# MYC_FS20.net
KiCad netlist of a schematic drawn in EAGLE
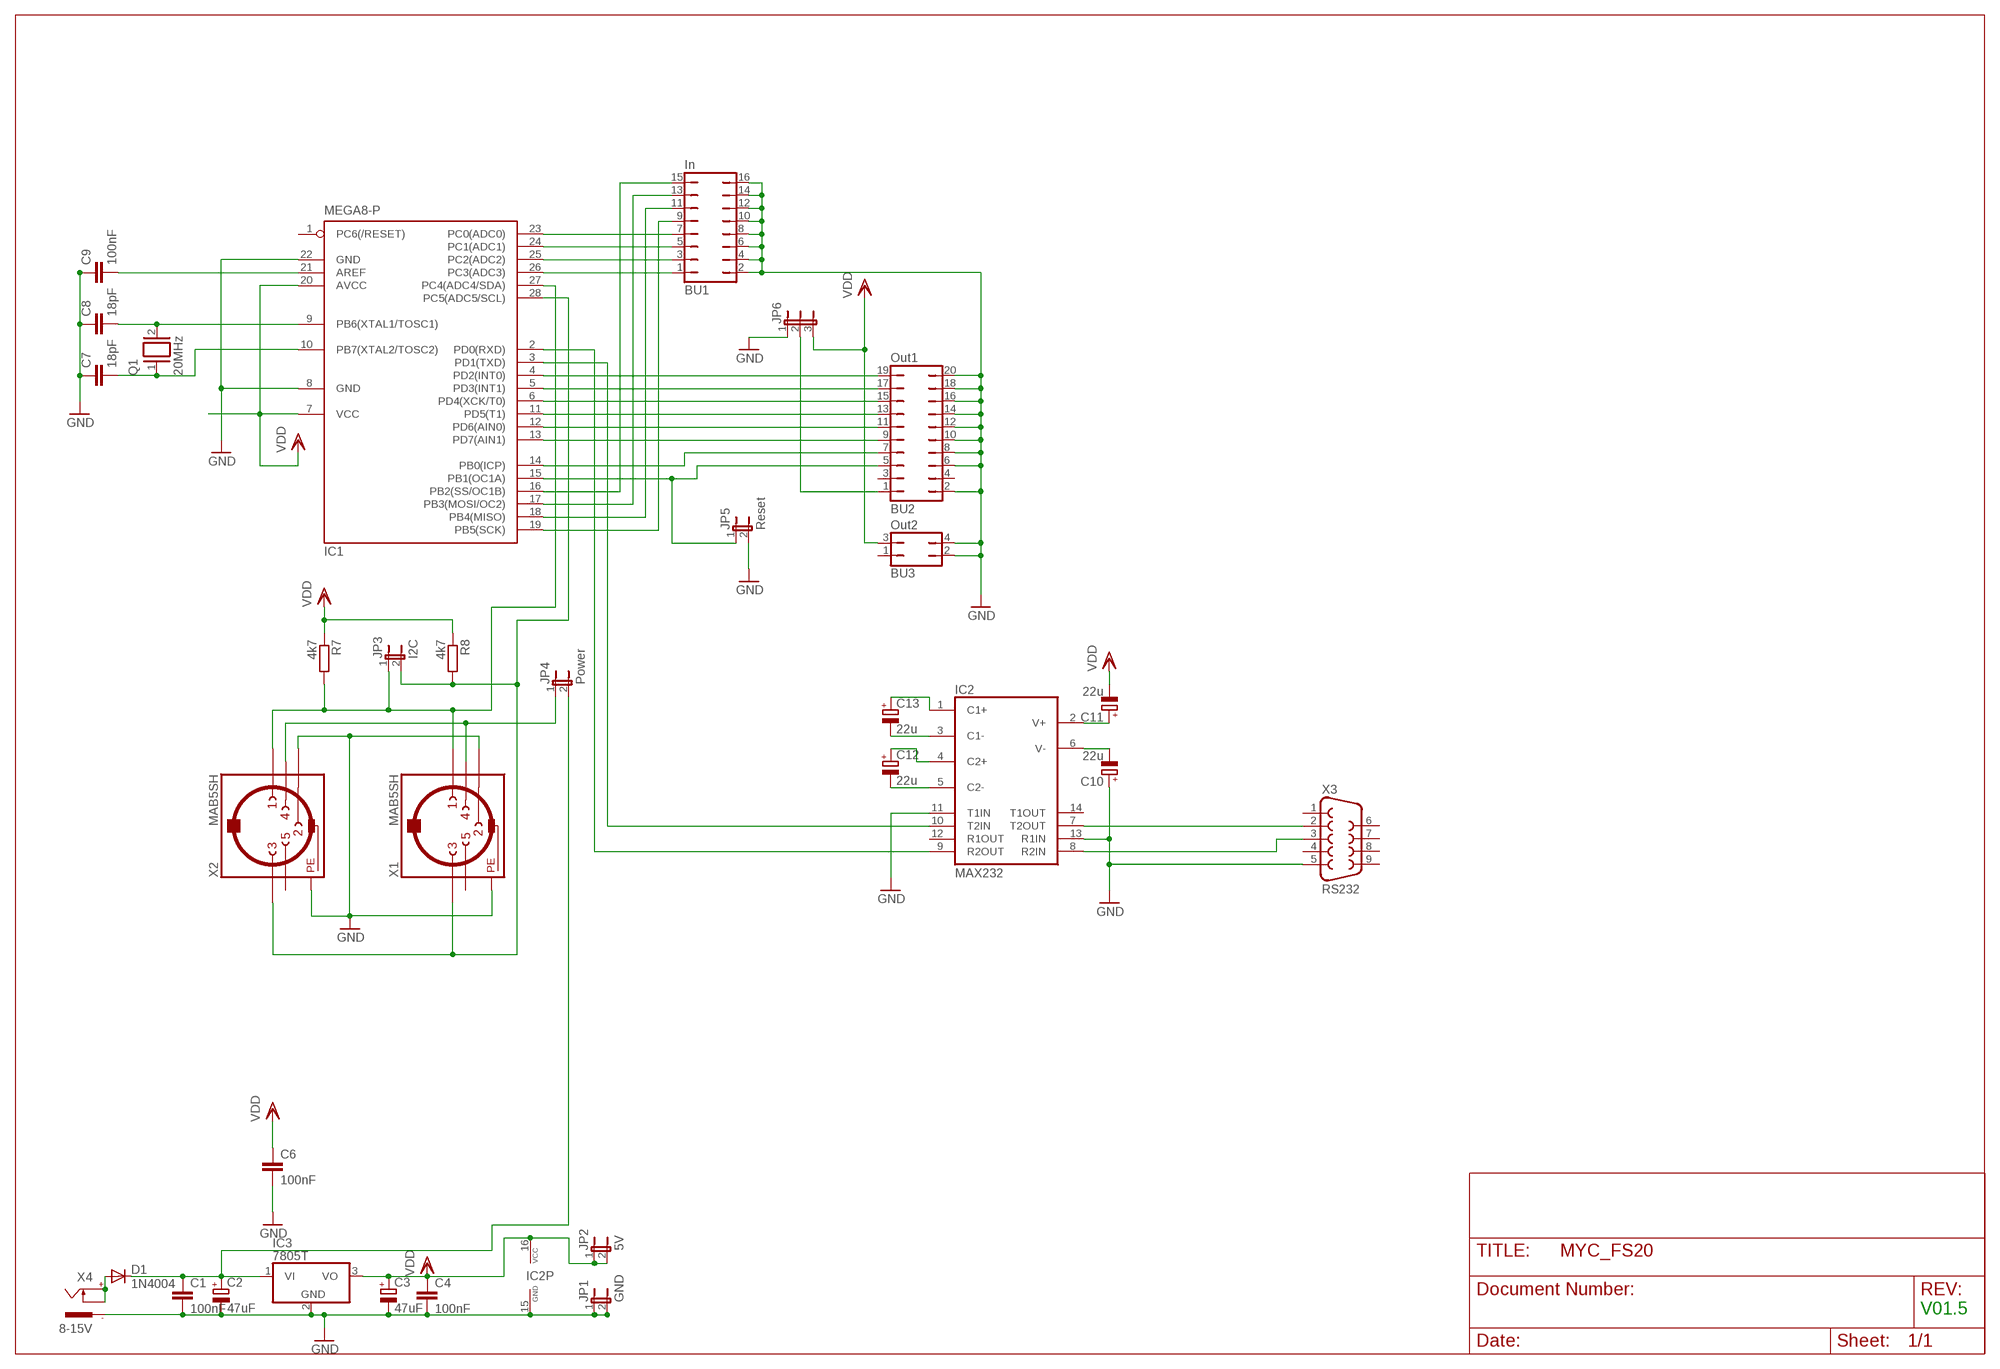
[diagram p0: schematic, sheet 1]

(export (version "E")
  (design (tool "Eeschema 10.0.6"))
  (components
    (comp (ref "BU1")
      (value "In")
      (footprint "eagle-import:JP8Q")
      (libsource (lib "eagle-import") (part "JP8Q"))
    )
    (comp (ref "BU2")
      (value "Out1")
      (footprint "eagle-import:JP10Q")
      (libsource (lib "eagle-import") (part "JP10Q"))
    )
    (comp (ref "BU3")
      (value "Out2")
      (footprint "eagle-import:JP2Q")
      (libsource (lib "eagle-import") (part "JP2Q"))
    )
    (comp (ref "C1")
      (value "100nF")
      (footprint "eagle-import:C050-025X075")
      (libsource (lib "eagle-import") (part "C-EU050-025X075"))
    )
    (comp (ref "C2")
      (value "47uF")
      (footprint "eagle-import:TT5D10")
      (libsource (lib "eagle-import") (part "CPOL-EUTT5D10"))
    )
    (comp (ref "C3")
      (value "47uF")
      (footprint "eagle-import:TT5D10")
      (libsource (lib "eagle-import") (part "CPOL-EUTT5D10"))
    )
    (comp (ref "C4")
      (value "100nF")
      (footprint "eagle-import:C050-025X075")
      (libsource (lib "eagle-import") (part "C-EU050-025X075"))
    )
    (comp (ref "C6")
      (value "100nF")
      (footprint "eagle-import:C050-025X075")
      (libsource (lib "eagle-import") (part "C-EU050-025X075"))
    )
    (comp (ref "C7")
      (value "18pF")
      (footprint "eagle-import:C050-025X075")
      (libsource (lib "eagle-import") (part "C-EU050-025X075"))
    )
    (comp (ref "C8")
      (value "18pF")
      (footprint "eagle-import:C050-025X075")
      (libsource (lib "eagle-import") (part "C-EU050-025X075"))
    )
    (comp (ref "C9")
      (value "100nF")
      (footprint "eagle-import:C050-025X075")
      (libsource (lib "eagle-import") (part "C-EU050-025X075"))
    )
    (comp (ref "C10")
      (value "22u")
      (footprint "eagle-import:TT5D7")
      (libsource (lib "eagle-import") (part "CPOL-EUTT5D7"))
    )
    (comp (ref "C11")
      (value "22u")
      (footprint "eagle-import:TT5D7")
      (libsource (lib "eagle-import") (part "CPOL-EUTT5D7"))
    )
    (comp (ref "C12")
      (value "22u")
      (footprint "eagle-import:TT5D7")
      (libsource (lib "eagle-import") (part "CPOL-EUTT5D7"))
    )
    (comp (ref "C13")
      (value "22u")
      (footprint "eagle-import:TT5D7")
      (libsource (lib "eagle-import") (part "CPOL-EUTT5D7"))
    )
    (comp (ref "D1")
      (value "1N4004")
      (footprint "eagle-import:DO41-10")
      (libsource (lib "eagle-import") (part "1N4004"))
    )
    (comp (ref "IC1")
      (value "MEGA8-P")
      (footprint "eagle-import:DIL28-3")
      (libsource (lib "eagle-import") (part "MEGA8-P"))
    )
    (comp (ref "IC2")
      (value "MAX232")
      (footprint "eagle-import:DIL16")
      (fields (field (name "MF") "MAXIM") (field (name "MPN") "MAX232ACPE+"))
      (libsource (lib "eagle-import") (part "MAX232"))
    )
    (comp (ref "IC3")
      (value "7805T")
      (footprint "eagle-import:TO220H")
      (libsource (lib "eagle-import") (part "78T05"))
    )
    (comp (ref "JP1")
      (value "GND")
      (footprint "eagle-import:JP1")
      (libsource (lib "eagle-import") (part "JP1E"))
    )
    (comp (ref "JP2")
      (value "5V")
      (footprint "eagle-import:JP1")
      (libsource (lib "eagle-import") (part "JP1E"))
    )
    (comp (ref "JP3")
      (value "I2C")
      (footprint "eagle-import:JP1")
      (libsource (lib "eagle-import") (part "JP1E"))
    )
    (comp (ref "JP4")
      (value "Power")
      (footprint "eagle-import:JP1")
      (libsource (lib "eagle-import") (part "JP1E"))
    )
    (comp (ref "JP5")
      (value "Reset")
      (footprint "eagle-import:JP1")
      (libsource (lib "eagle-import") (part "JP1E"))
    )
    (comp (ref "JP6")
      (value "JP2E")
      (footprint "eagle-import:JP2")
      (libsource (lib "eagle-import") (part "JP2E"))
    )
    (comp (ref "Q1")
      (value "20MHz")
      (footprint "eagle-import:QS")
      (libsource (lib "eagle-import") (part "XTAL/S"))
    )
    (comp (ref "R7")
      (value "4k7")
      (footprint "eagle-import:0207_5V")
      (libsource (lib "eagle-import") (part "R-EU_0207/5V"))
    )
    (comp (ref "R8")
      (value "4k7")
      (footprint "eagle-import:0207_5V")
      (libsource (lib "eagle-import") (part "R-EU_0207/5V"))
    )
    (comp (ref "X1")
      (value "MAB5SH")
      (footprint "eagle-import:MAB5SH")
      (libsource (lib "eagle-import") (part "MAB5SH"))
    )
    (comp (ref "X2")
      (value "MAB5SH")
      (footprint "eagle-import:MAB5SH")
      (libsource (lib "eagle-import") (part "MAB5SH"))
    )
    (comp (ref "X3")
      (value "RS232")
      (footprint "eagle-import:F09H")
      (libsource (lib "eagle-import") (part "F09H"))
    )
    (comp (ref "X4")
      (value "8-15V")
      (footprint "eagle-import:737992-5")
      (libsource (lib "eagle-import") (part "737992-55"))
    )
  )
  (nets
    (net (code "1") (name "GND") (class "Default")
      (node (ref "BU1") (pin "10") (pinfunction "10_10") (pintype "passive"))
      (node (ref "BU1") (pin "12") (pinfunction "12_12") (pintype "passive"))
      (node (ref "BU1") (pin "14") (pinfunction "14_14") (pintype "passive"))
      (node (ref "BU1") (pin "16") (pinfunction "16_16") (pintype "passive"))
      (node (ref "BU1") (pin "2") (pinfunction "2_2") (pintype "passive"))
      (node (ref "BU1") (pin "4") (pinfunction "4_4") (pintype "passive"))
      (node (ref "BU1") (pin "6") (pinfunction "6_6") (pintype "passive"))
      (node (ref "BU1") (pin "8") (pinfunction "8_8") (pintype "passive"))
      (node (ref "BU2") (pin "10") (pinfunction "10_10") (pintype "passive"))
      (node (ref "BU2") (pin "12") (pinfunction "12_12") (pintype "passive"))
      (node (ref "BU2") (pin "14") (pinfunction "14_14") (pintype "passive"))
      (node (ref "BU2") (pin "16") (pinfunction "16_16") (pintype "passive"))
      (node (ref "BU2") (pin "18") (pinfunction "18_18") (pintype "passive"))
      (node (ref "BU2") (pin "2") (pinfunction "2_2") (pintype "passive"))
      (node (ref "BU2") (pin "20") (pinfunction "20_20") (pintype "passive"))
      (node (ref "BU2") (pin "6") (pinfunction "6_6") (pintype "passive"))
      (node (ref "BU2") (pin "8") (pinfunction "8_8") (pintype "passive"))
      (node (ref "BU3") (pin "2") (pinfunction "2_2") (pintype "passive"))
      (node (ref "BU3") (pin "4") (pinfunction "4_4") (pintype "passive"))
      (node (ref "C1") (pin "2") (pinfunction "2_2") (pintype "passive"))
      (node (ref "C10") (pin "+") (pinfunction "+_+") (pintype "passive"))
      (node (ref "C2") (pin "-") (pinfunction "-_-") (pintype "passive"))
      (node (ref "C3") (pin "-") (pinfunction "-_-") (pintype "passive"))
      (node (ref "C4") (pin "2") (pinfunction "2_2") (pintype "passive"))
      (node (ref "C6") (pin "2") (pinfunction "2_2") (pintype "passive"))
      (node (ref "C7") (pin "1") (pinfunction "1_1") (pintype "passive"))
      (node (ref "C8") (pin "1") (pinfunction "1_1") (pintype "passive"))
      (node (ref "C9") (pin "1") (pinfunction "1_1") (pintype "passive"))
      (node (ref "IC1") (pin "22") (pinfunction "GND_22") (pintype "power_in"))
      (node (ref "IC1") (pin "8") (pinfunction "GND_8") (pintype "power_in"))
      (node (ref "IC2") (pin "11") (pinfunction "T1IN_11") (pintype "input"))
      (node (ref "IC2") (pin "13") (pinfunction "R1IN_13") (pintype "input"))
      (node (ref "IC2") (pin "15") (pinfunction "GND_15") (pintype "power_in"))
      (node (ref "IC3") (pin "2") (pinfunction "GND_2") (pintype "passive"))
      (node (ref "JP1") (pin "1") (pinfunction "1_1") (pintype "passive"))
      (node (ref "JP1") (pin "2") (pinfunction "2_2") (pintype "passive"))
      (node (ref "JP5") (pin "2") (pinfunction "2_2") (pintype "passive"))
      (node (ref "JP6") (pin "1") (pinfunction "1_1") (pintype "passive"))
      (node (ref "X1") (pin "2") (pinfunction "2_2") (pintype "passive"))
      (node (ref "X1") (pin "PE") (pinfunction "PE_PE") (pintype "power_in"))
      (node (ref "X1") (pin "PE@") (pinfunction "PE_PE@") (pintype "power_in"))
      (node (ref "X2") (pin "2") (pinfunction "2_2") (pintype "passive"))
      (node (ref "X2") (pin "PE") (pinfunction "PE_PE") (pintype "power_in"))
      (node (ref "X2") (pin "PE@") (pinfunction "PE_PE@") (pintype "power_in"))
      (node (ref "X3") (pin "5") (pinfunction "5_5") (pintype "passive"))
      (node (ref "X4") (pin "-1") (pinfunction "-1_-1") (pintype "passive"))
    )
    (net (code "2") (name "Net-(BU2-Pad1)") (class "Default")
      (node (ref "BU2") (pin "1") (pinfunction "1_1") (pintype "passive"))
      (node (ref "JP6") (pin "2") (pinfunction "2_2") (pintype "passive"))
    )
    (net (code "3") (name "Net-(D1-PadA)") (class "Default")
      (node (ref "D1") (pin "A") (pinfunction "A_A") (pintype "passive"))
      (node (ref "X4") (pin "+") (pinfunction "+_+") (pintype "passive"))
      (node (ref "X4") (pin "K") (pinfunction "K_K") (pintype "passive"))
    )
    (net (code "4") (name "Net-(IC1-AREF)") (class "Default")
      (node (ref "C9") (pin "2") (pinfunction "2_2") (pintype "passive"))
      (node (ref "IC1") (pin "21") (pinfunction "AREF_21") (pintype "passive"))
    )
    (net (code "5") (name "Net-(IC1-PB0(ICP))") (class "Default")
      (node (ref "BU2") (pin "7") (pinfunction "7_7") (pintype "passive"))
      (node (ref "IC1") (pin "14") (pinfunction "PB0(ICP)_14") (pintype "bidirectional"))
    )
    (net (code "6") (name "Net-(IC1-PB1(OC1A))") (class "Default")
      (node (ref "BU2") (pin "5") (pinfunction "5_5") (pintype "passive"))
      (node (ref "IC1") (pin "15") (pinfunction "PB1(OC1A)_15") (pintype "bidirectional"))
      (node (ref "JP5") (pin "1") (pinfunction "1_1") (pintype "passive"))
    )
    (net (code "7") (name "Net-(IC1-PB2(SS{slash}OC1B))") (class "Default")
      (node (ref "BU1") (pin "15") (pinfunction "15_15") (pintype "passive"))
      (node (ref "IC1") (pin "16") (pinfunction "PB2(SS/OC1B)_16") (pintype "bidirectional"))
    )
    (net (code "8") (name "Net-(IC1-PB3(MOSI{slash}OC2))") (class "Default")
      (node (ref "BU1") (pin "13") (pinfunction "13_13") (pintype "passive"))
      (node (ref "IC1") (pin "17") (pinfunction "PB3(MOSI/OC2)_17") (pintype "bidirectional"))
    )
    (net (code "9") (name "Net-(IC1-PB4(MISO))") (class "Default")
      (node (ref "BU1") (pin "11") (pinfunction "11_11") (pintype "passive"))
      (node (ref "IC1") (pin "18") (pinfunction "PB4(MISO)_18") (pintype "bidirectional"))
    )
    (net (code "10") (name "Net-(IC1-PB5(SCK))") (class "Default")
      (node (ref "BU1") (pin "9") (pinfunction "9_9") (pintype "passive"))
      (node (ref "IC1") (pin "19") (pinfunction "PB5(SCK)_19") (pintype "bidirectional"))
    )
    (net (code "11") (name "Net-(IC1-PB6(XTAL1{slash}TOSC1))") (class "Default")
      (node (ref "C8") (pin "2") (pinfunction "2_2") (pintype "passive"))
      (node (ref "IC1") (pin "9") (pinfunction "PB6(XTAL1/TOSC1)_9") (pintype "bidirectional"))
      (node (ref "Q1") (pin "2") (pinfunction "2_2") (pintype "passive"))
    )
    (net (code "12") (name "Net-(IC1-PB7(XTAL2{slash}TOSC2))") (class "Default")
      (node (ref "C7") (pin "2") (pinfunction "2_2") (pintype "passive"))
      (node (ref "IC1") (pin "10") (pinfunction "PB7(XTAL2/TOSC2)_10") (pintype "bidirectional"))
      (node (ref "Q1") (pin "1") (pinfunction "1_1") (pintype "passive"))
    )
    (net (code "13") (name "Net-(IC1-PC0(ADC0))") (class "Default")
      (node (ref "BU1") (pin "7") (pinfunction "7_7") (pintype "passive"))
      (node (ref "IC1") (pin "23") (pinfunction "PC0(ADC0)_23") (pintype "bidirectional"))
    )
    (net (code "14") (name "Net-(IC1-PC1(ADC1))") (class "Default")
      (node (ref "BU1") (pin "5") (pinfunction "5_5") (pintype "passive"))
      (node (ref "IC1") (pin "24") (pinfunction "PC1(ADC1)_24") (pintype "bidirectional"))
    )
    (net (code "15") (name "Net-(IC1-PC2(ADC2))") (class "Default")
      (node (ref "BU1") (pin "3") (pinfunction "3_3") (pintype "passive"))
      (node (ref "IC1") (pin "25") (pinfunction "PC2(ADC2)_25") (pintype "bidirectional"))
    )
    (net (code "16") (name "Net-(IC1-PC3(ADC3))") (class "Default")
      (node (ref "BU1") (pin "1") (pinfunction "1_1") (pintype "passive"))
      (node (ref "IC1") (pin "26") (pinfunction "PC3(ADC3)_26") (pintype "bidirectional"))
    )
    (net (code "17") (name "Net-(IC1-PC4(ADC4{slash}SDA))") (class "Default")
      (node (ref "IC1") (pin "27") (pinfunction "PC4(ADC4/SDA)_27") (pintype "bidirectional"))
      (node (ref "JP3") (pin "1") (pinfunction "1_1") (pintype "passive"))
      (node (ref "R7") (pin "2") (pinfunction "2_2") (pintype "passive"))
      (node (ref "X1") (pin "1") (pinfunction "1_1") (pintype "passive"))
      (node (ref "X2") (pin "1") (pinfunction "1_1") (pintype "passive"))
    )
    (net (code "18") (name "Net-(IC1-PC5(ADC5{slash}SCL))") (class "Default")
      (node (ref "IC1") (pin "28") (pinfunction "PC5(ADC5/SCL)_28") (pintype "bidirectional"))
      (node (ref "JP3") (pin "2") (pinfunction "2_2") (pintype "passive"))
      (node (ref "R8") (pin "2") (pinfunction "2_2") (pintype "passive"))
      (node (ref "X1") (pin "3") (pinfunction "3_3") (pintype "passive"))
      (node (ref "X2") (pin "3") (pinfunction "3_3") (pintype "passive"))
    )
    (net (code "19") (name "Net-(IC1-PD0(RXD))") (class "Default")
      (node (ref "IC1") (pin "2") (pinfunction "PD0(RXD)_2") (pintype "bidirectional"))
      (node (ref "IC2") (pin "9") (pinfunction "R2OUT_9") (pintype "output"))
    )
    (net (code "20") (name "Net-(IC1-PD1(TXD))") (class "Default")
      (node (ref "IC1") (pin "3") (pinfunction "PD1(TXD)_3") (pintype "bidirectional"))
      (node (ref "IC2") (pin "10") (pinfunction "T2IN_10") (pintype "input"))
    )
    (net (code "21") (name "Net-(IC1-PD2(INT0))") (class "Default")
      (node (ref "BU2") (pin "19") (pinfunction "19_19") (pintype "passive"))
      (node (ref "IC1") (pin "4") (pinfunction "PD2(INT0)_4") (pintype "bidirectional"))
    )
    (net (code "22") (name "Net-(IC1-PD3(INT1))") (class "Default")
      (node (ref "BU2") (pin "17") (pinfunction "17_17") (pintype "passive"))
      (node (ref "IC1") (pin "5") (pinfunction "PD3(INT1)_5") (pintype "bidirectional"))
    )
    (net (code "23") (name "Net-(IC1-PD4(XCK{slash}T0))") (class "Default")
      (node (ref "BU2") (pin "15") (pinfunction "15_15") (pintype "passive"))
      (node (ref "IC1") (pin "6") (pinfunction "PD4(XCK/T0)_6") (pintype "bidirectional"))
    )
    (net (code "24") (name "Net-(IC1-PD5(T1))") (class "Default")
      (node (ref "BU2") (pin "13") (pinfunction "13_13") (pintype "passive"))
      (node (ref "IC1") (pin "11") (pinfunction "PD5(T1)_11") (pintype "bidirectional"))
    )
    (net (code "25") (name "Net-(IC1-PD6(AIN0))") (class "Default")
      (node (ref "BU2") (pin "11") (pinfunction "11_11") (pintype "passive"))
      (node (ref "IC1") (pin "12") (pinfunction "PD6(AIN0)_12") (pintype "bidirectional"))
    )
    (net (code "26") (name "Net-(IC1-PD7(AIN1))") (class "Default")
      (node (ref "BU2") (pin "9") (pinfunction "9_9") (pintype "passive"))
      (node (ref "IC1") (pin "13") (pinfunction "PD7(AIN1)_13") (pintype "bidirectional"))
    )
    (net (code "27") (name "Net-(IC2A-C1+)") (class "Default")
      (node (ref "C13") (pin "+") (pinfunction "+_+") (pintype "passive"))
      (node (ref "IC2") (pin "1") (pinfunction "C1+_1") (pintype "bidirectional"))
    )
    (net (code "28") (name "Net-(IC2A-C1-)") (class "Default")
      (node (ref "C13") (pin "-") (pinfunction "-_-") (pintype "passive"))
      (node (ref "IC2") (pin "3") (pinfunction "C1-_3") (pintype "bidirectional"))
    )
    (net (code "29") (name "Net-(IC2A-C2+)") (class "Default")
      (node (ref "C12") (pin "+") (pinfunction "+_+") (pintype "passive"))
      (node (ref "IC2") (pin "4") (pinfunction "C2+_4") (pintype "bidirectional"))
    )
    (net (code "30") (name "Net-(IC2A-C2-)") (class "Default")
      (node (ref "C12") (pin "-") (pinfunction "-_-") (pintype "passive"))
      (node (ref "IC2") (pin "5") (pinfunction "C2-_5") (pintype "bidirectional"))
    )
    (net (code "31") (name "Net-(IC2A-R2IN)") (class "Default")
      (node (ref "IC2") (pin "8") (pinfunction "R2IN_8") (pintype "input"))
      (node (ref "X3") (pin "3") (pinfunction "3_3") (pintype "passive"))
    )
    (net (code "32") (name "Net-(IC2A-T2OUT)") (class "Default")
      (node (ref "IC2") (pin "7") (pinfunction "T2OUT_7") (pintype "output"))
      (node (ref "X3") (pin "2") (pinfunction "2_2") (pintype "passive"))
    )
    (net (code "33") (name "Net-(IC2A-V+)") (class "Default")
      (node (ref "C11") (pin "+") (pinfunction "+_+") (pintype "passive"))
      (node (ref "IC2") (pin "2") (pinfunction "V+_2") (pintype "bidirectional"))
    )
    (net (code "34") (name "Net-(IC2A-V-)") (class "Default")
      (node (ref "C10") (pin "-") (pinfunction "-_-") (pintype "passive"))
      (node (ref "IC2") (pin "6") (pinfunction "V-_6") (pintype "bidirectional"))
    )
    (net (code "35") (name "Net-(IC3-VI)") (class "Default")
      (node (ref "C1") (pin "1") (pinfunction "1_1") (pintype "passive"))
      (node (ref "C2") (pin "+") (pinfunction "+_+") (pintype "passive"))
      (node (ref "D1") (pin "C") (pinfunction "C_C") (pintype "passive"))
      (node (ref "IC3") (pin "1") (pinfunction "VI_1") (pintype "input"))
      (node (ref "JP4") (pin "2") (pinfunction "2_2") (pintype "passive"))
    )
    (net (code "36") (name "Net-(JP4-Pad1)") (class "Default")
      (node (ref "JP4") (pin "1") (pinfunction "1_1") (pintype "passive"))
      (node (ref "X1") (pin "4") (pinfunction "4_4") (pintype "passive"))
      (node (ref "X2") (pin "4") (pinfunction "4_4") (pintype "passive"))
    )
    (net (code "37") (name "VDD") (class "Default")
      (node (ref "BU3") (pin "3") (pinfunction "3_3") (pintype "passive"))
      (node (ref "C11") (pin "-") (pinfunction "-_-") (pintype "passive"))
      (node (ref "C3") (pin "+") (pinfunction "+_+") (pintype "passive"))
      (node (ref "C4") (pin "1") (pinfunction "1_1") (pintype "passive"))
      (node (ref "C6") (pin "1") (pinfunction "1_1") (pintype "passive"))
      (node (ref "IC1") (pin "20") (pinfunction "AVCC_20") (pintype "power_in"))
      (node (ref "IC1") (pin "7") (pinfunction "VCC_7") (pintype "power_in"))
      (node (ref "IC2") (pin "16") (pinfunction "VCC_16") (pintype "power_in"))
      (node (ref "IC3") (pin "3") (pinfunction "VO_3") (pintype "passive"))
      (node (ref "JP2") (pin "1") (pinfunction "1_1") (pintype "passive"))
      (node (ref "JP2") (pin "2") (pinfunction "2_2") (pintype "passive"))
      (node (ref "JP6") (pin "3") (pinfunction "3_3") (pintype "passive"))
      (node (ref "R7") (pin "1") (pinfunction "1_1") (pintype "passive"))
      (node (ref "R8") (pin "1") (pinfunction "1_1") (pintype "passive"))
    )
    (net (code "38") (name "unconnected-(BU2-Pad3)") (class "Default")
      (node (ref "BU2") (pin "3") (pinfunction "3_3") (pintype "passive"))
    )
    (net (code "39") (name "unconnected-(BU2-Pad4)") (class "Default")
      (node (ref "BU2") (pin "4") (pinfunction "4_4") (pintype "passive"))
    )
    (net (code "40") (name "unconnected-(BU3-Pad1)") (class "Default")
      (node (ref "BU3") (pin "1") (pinfunction "1_1") (pintype "passive"))
    )
    (net (code "41") (name "unconnected-(IC1-PC6({slash}RESET)-Pad1)") (class "Default")
      (node (ref "IC1") (pin "1") (pinfunction "PC6(/RESET)_1") (pintype "bidirectional"))
    )
    (net (code "42") (name "unconnected-(IC2A-R1OUT-Pad12)") (class "Default")
      (node (ref "IC2") (pin "12") (pinfunction "R1OUT_12") (pintype "output"))
    )
    (net (code "43") (name "unconnected-(IC2A-T1OUT-Pad14)") (class "Default")
      (node (ref "IC2") (pin "14") (pinfunction "T1OUT_14") (pintype "output"))
    )
    (net (code "44") (name "unconnected-(X1-Pad5)") (class "Default")
      (node (ref "X1") (pin "5") (pinfunction "5_5") (pintype "passive"))
    )
    (net (code "45") (name "unconnected-(X2-Pad5)") (class "Default")
      (node (ref "X2") (pin "5") (pinfunction "5_5") (pintype "passive"))
    )
    (net (code "46") (name "unconnected-(X3-Pad1)") (class "Default")
      (node (ref "X3") (pin "1") (pinfunction "1_1") (pintype "passive"))
    )
    (net (code "47") (name "unconnected-(X3-Pad4)") (class "Default")
      (node (ref "X3") (pin "4") (pinfunction "4_4") (pintype "passive"))
    )
    (net (code "48") (name "unconnected-(X3-Pad6)") (class "Default")
      (node (ref "X3") (pin "6") (pinfunction "6_6") (pintype "passive"))
    )
    (net (code "49") (name "unconnected-(X3-Pad7)") (class "Default")
      (node (ref "X3") (pin "7") (pinfunction "7_7") (pintype "passive"))
    )
    (net (code "50") (name "unconnected-(X3-Pad8)") (class "Default")
      (node (ref "X3") (pin "8") (pinfunction "8_8") (pintype "passive"))
    )
    (net (code "51") (name "unconnected-(X3-Pad9)") (class "Default")
      (node (ref "X3") (pin "9") (pinfunction "9_9") (pintype "passive"))
    )
    (net (code "52") (name "unconnected-(X4-Pad-2)") (class "Default")
      (node (ref "X4") (pin "-2") (pinfunction "-2_-2") (pintype "passive"))
    )
  )
)
